# dhunter_ispHeader.net
KiCad netlist of a schematic drawn in EAGLE
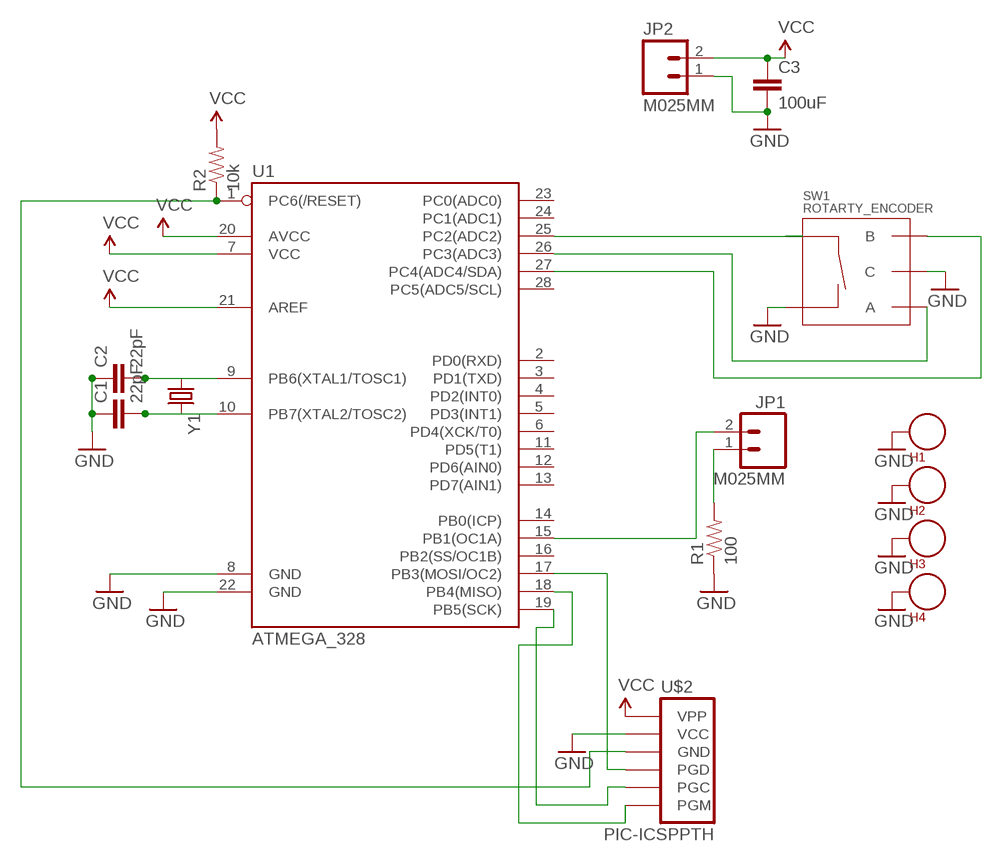
[diagram p0: schematic, sheet 1]

(export (version "E")
  (design (tool "Eeschema 10.0.6"))
  (components
    (comp (ref "C1")
      (value "22pF")
      (footprint "eagle-import:CAP-PTH-SMALLEZ")
      (libsource (lib "eagle-import") (part "CAPEZ"))
    )
    (comp (ref "C2")
      (value "22pF")
      (footprint "eagle-import:CAP-PTH-SMALLEZ")
      (libsource (lib "eagle-import") (part "CAPEZ"))
    )
    (comp (ref "C3")
      (value "100uF")
      (footprint "eagle-import:CAP-PTH-SMALLEZ")
      (libsource (lib "eagle-import") (part "CAPEZ"))
    )
    (comp (ref "H1")
      (value "SEW_HOLE")
      (footprint "eagle-import:SIMPLE_HOLE")
      (libsource (lib "eagle-import") (part "SEW_HOLE"))
    )
    (comp (ref "H2")
      (value "SEW_HOLE")
      (footprint "eagle-import:SIMPLE_HOLE")
      (libsource (lib "eagle-import") (part "SEW_HOLE"))
    )
    (comp (ref "H3")
      (value "SEW_HOLE")
      (footprint "eagle-import:SIMPLE_HOLE")
      (libsource (lib "eagle-import") (part "SEW_HOLE"))
    )
    (comp (ref "H4")
      (value "SEW_HOLE")
      (footprint "eagle-import:SIMPLE_HOLE")
      (libsource (lib "eagle-import") (part "SEW_HOLE"))
    )
    (comp (ref "JP1")
      (value "M025MM")
      (footprint "eagle-import:SCREWTERMINAL-5MM-2")
      (libsource (lib "eagle-import") (part "M025MM"))
    )
    (comp (ref "JP2")
      (value "M025MM")
      (footprint "eagle-import:SCREWTERMINAL-5MM-2")
      (libsource (lib "eagle-import") (part "M025MM"))
    )
    (comp (ref "R1")
      (value "100")
      (footprint "eagle-import:AXIAL-0.3EZ")
      (libsource (lib "eagle-import") (part "RESISTOREZ"))
    )
    (comp (ref "R2")
      (value "10k")
      (footprint "eagle-import:AXIAL-0.3EZ")
      (libsource (lib "eagle-import") (part "RESISTOREZ"))
    )
    (comp (ref "SW1")
      (value "ROTARTY_ENCODER")
      (footprint "eagle-import:ROTARY_ENC_PLAIN")
      (libsource (lib "eagle-import") (part "ROTARTY_ENCODER"))
    )
    (comp (ref "U$2")
      (value "PIC-ICSPPTH")
      (footprint "eagle-import:MOLEX-1X6")
      (libsource (lib "eagle-import") (part "PIC-ICSPPTH"))
    )
    (comp (ref "U1")
      (value "ATMEGA_328")
      (footprint "eagle-import:DIL28-3")
      (libsource (lib "eagle-import") (part "ATMEGA328P_PDIP"))
    )
    (comp (ref "Y1")
      (value "CRYSTALHC49US")
      (footprint "eagle-import:HC49US")
      (libsource (lib "eagle-import") (part "CRYSTALHC49US"))
    )
  )
  (nets
    (net (code "1") (name "GND") (class "Default")
      (node (ref "C1") (pin "1") (pinfunction "1_1") (pintype "passive"))
      (node (ref "C2") (pin "1") (pinfunction "1_1") (pintype "passive"))
      (node (ref "C3") (pin "2") (pinfunction "2_2") (pintype "passive"))
      (node (ref "H1") (pin "P$1") (pinfunction "P$1_P$1") (pintype "bidirectional"))
      (node (ref "H2") (pin "P$1") (pinfunction "P$1_P$1") (pintype "bidirectional"))
      (node (ref "H3") (pin "P$1") (pinfunction "P$1_P$1") (pintype "bidirectional"))
      (node (ref "H4") (pin "P$1") (pinfunction "P$1_P$1") (pintype "bidirectional"))
      (node (ref "JP2") (pin "1") (pinfunction "1_1") (pintype "passive"))
      (node (ref "R1") (pin "P$1") (pinfunction "1_P$1") (pintype "passive"))
      (node (ref "SW1") (pin "C") (pinfunction "C_C") (pintype "bidirectional"))
      (node (ref "SW1") (pin "SW-") (pinfunction "SW-_SW-") (pintype "bidirectional"))
      (node (ref "U$2") (pin "5") (pinfunction "VCC_5") (pintype "bidirectional"))
      (node (ref "U1") (pin "22") (pinfunction "GND_22") (pintype "bidirectional"))
      (node (ref "U1") (pin "8") (pinfunction "GND_8") (pintype "bidirectional"))
    )
    (net (code "2") (name "Net-(R1-2)") (class "Default")
      (node (ref "JP1") (pin "1") (pinfunction "1_1") (pintype "passive"))
      (node (ref "R1") (pin "P$2") (pinfunction "2_P$2") (pintype "passive"))
    )
    (net (code "3") (name "Net-(R2-1)") (class "Default")
      (node (ref "R2") (pin "P$1") (pinfunction "1_P$1") (pintype "passive"))
      (node (ref "U$2") (pin "4") (pinfunction "GND_4") (pintype "bidirectional"))
      (node (ref "U1") (pin "1") (pinfunction "PC6(/RESET)_1") (pintype "bidirectional"))
    )
    (net (code "4") (name "Net-(U$2-PGC)") (class "Default")
      (node (ref "U$2") (pin "2") (pinfunction "PGC_2") (pintype "bidirectional"))
      (node (ref "U1") (pin "19") (pinfunction "PB5(SCK)_19") (pintype "bidirectional"))
    )
    (net (code "5") (name "Net-(U$2-PGD)") (class "Default")
      (node (ref "U$2") (pin "3") (pinfunction "PGD_3") (pintype "bidirectional"))
      (node (ref "U1") (pin "17") (pinfunction "PB3(MOSI/OC2)_17") (pintype "bidirectional"))
    )
    (net (code "6") (name "Net-(U$2-PGM)") (class "Default")
      (node (ref "U$2") (pin "1") (pinfunction "PGM_1") (pintype "bidirectional"))
      (node (ref "U1") (pin "18") (pinfunction "PB4(MISO)_18") (pintype "bidirectional"))
    )
    (net (code "7") (name "Net-(U1-PB1(OC1A))") (class "Default")
      (node (ref "JP1") (pin "2") (pinfunction "2_2") (pintype "passive"))
      (node (ref "U1") (pin "15") (pinfunction "PB1(OC1A)_15") (pintype "bidirectional"))
    )
    (net (code "8") (name "Net-(U1-PB6(XTAL1{slash}TOSC1))") (class "Default")
      (node (ref "C2") (pin "2") (pinfunction "2_2") (pintype "passive"))
      (node (ref "U1") (pin "9") (pinfunction "PB6(XTAL1/TOSC1)_9") (pintype "bidirectional"))
      (node (ref "Y1") (pin "1") (pinfunction "1_1") (pintype "passive"))
    )
    (net (code "9") (name "Net-(U1-PB7(XTAL2{slash}TOSC2))") (class "Default")
      (node (ref "C1") (pin "2") (pinfunction "2_2") (pintype "passive"))
      (node (ref "U1") (pin "10") (pinfunction "PB7(XTAL2/TOSC2)_10") (pintype "bidirectional"))
      (node (ref "Y1") (pin "2") (pinfunction "2_2") (pintype "passive"))
    )
    (net (code "10") (name "Net-(U1-PC2(ADC2))") (class "Default")
      (node (ref "SW1") (pin "SW+") (pinfunction "SW+_SW+") (pintype "bidirectional"))
      (node (ref "U1") (pin "25") (pinfunction "PC2(ADC2)_25") (pintype "bidirectional"))
    )
    (net (code "11") (name "Net-(U1-PC3(ADC3))") (class "Default")
      (node (ref "SW1") (pin "A") (pinfunction "A_A") (pintype "bidirectional"))
      (node (ref "U1") (pin "26") (pinfunction "PC3(ADC3)_26") (pintype "bidirectional"))
    )
    (net (code "12") (name "Net-(U1-PC4(ADC4{slash}SDA))") (class "Default")
      (node (ref "SW1") (pin "B") (pinfunction "B_B") (pintype "bidirectional"))
      (node (ref "U1") (pin "27") (pinfunction "PC4(ADC4/SDA)_27") (pintype "bidirectional"))
    )
    (net (code "13") (name "VCC") (class "Default")
      (node (ref "C3") (pin "1") (pinfunction "1_1") (pintype "passive"))
      (node (ref "JP2") (pin "2") (pinfunction "2_2") (pintype "passive"))
      (node (ref "R2") (pin "P$2") (pinfunction "2_P$2") (pintype "passive"))
      (node (ref "U$2") (pin "6") (pinfunction "VPP_6") (pintype "bidirectional"))
      (node (ref "U1") (pin "20") (pinfunction "AVCC_20") (pintype "bidirectional"))
      (node (ref "U1") (pin "21") (pinfunction "AREF_21") (pintype "bidirectional"))
      (node (ref "U1") (pin "7") (pinfunction "VCC_7") (pintype "bidirectional"))
    )
    (net (code "14") (name "unconnected-(U1-PB0(ICP)-Pad14)") (class "Default")
      (node (ref "U1") (pin "14") (pinfunction "PB0(ICP)_14") (pintype "bidirectional"))
    )
    (net (code "15") (name "unconnected-(U1-PB2(SS{slash}OC1B)-Pad16)") (class "Default")
      (node (ref "U1") (pin "16") (pinfunction "PB2(SS/OC1B)_16") (pintype "bidirectional"))
    )
    (net (code "16") (name "unconnected-(U1-PC0(ADC0)-Pad23)") (class "Default")
      (node (ref "U1") (pin "23") (pinfunction "PC0(ADC0)_23") (pintype "bidirectional"))
    )
    (net (code "17") (name "unconnected-(U1-PC1(ADC1)-Pad24)") (class "Default")
      (node (ref "U1") (pin "24") (pinfunction "PC1(ADC1)_24") (pintype "bidirectional"))
    )
    (net (code "18") (name "unconnected-(U1-PC5(ADC5{slash}SCL)-Pad28)") (class "Default")
      (node (ref "U1") (pin "28") (pinfunction "PC5(ADC5/SCL)_28") (pintype "bidirectional"))
    )
    (net (code "19") (name "unconnected-(U1-PD0(RXD)-Pad2)") (class "Default")
      (node (ref "U1") (pin "2") (pinfunction "PD0(RXD)_2") (pintype "bidirectional"))
    )
    (net (code "20") (name "unconnected-(U1-PD1(TXD)-Pad3)") (class "Default")
      (node (ref "U1") (pin "3") (pinfunction "PD1(TXD)_3") (pintype "bidirectional"))
    )
    (net (code "21") (name "unconnected-(U1-PD2(INT0)-Pad4)") (class "Default")
      (node (ref "U1") (pin "4") (pinfunction "PD2(INT0)_4") (pintype "bidirectional"))
    )
    (net (code "22") (name "unconnected-(U1-PD3(INT1)-Pad5)") (class "Default")
      (node (ref "U1") (pin "5") (pinfunction "PD3(INT1)_5") (pintype "bidirectional"))
    )
    (net (code "23") (name "unconnected-(U1-PD4(XCK{slash}T0)-Pad6)") (class "Default")
      (node (ref "U1") (pin "6") (pinfunction "PD4(XCK/T0)_6") (pintype "bidirectional"))
    )
    (net (code "24") (name "unconnected-(U1-PD5(T1)-Pad11)") (class "Default")
      (node (ref "U1") (pin "11") (pinfunction "PD5(T1)_11") (pintype "bidirectional"))
    )
    (net (code "25") (name "unconnected-(U1-PD6(AIN0)-Pad12)") (class "Default")
      (node (ref "U1") (pin "12") (pinfunction "PD6(AIN0)_12") (pintype "bidirectional"))
    )
    (net (code "26") (name "unconnected-(U1-PD7(AIN1)-Pad13)") (class "Default")
      (node (ref "U1") (pin "13") (pinfunction "PD7(AIN1)_13") (pintype "bidirectional"))
    )
  )
)
